# RPi_Zero_W_Breakout.net
KiCad netlist of a schematic drawn in EAGLE
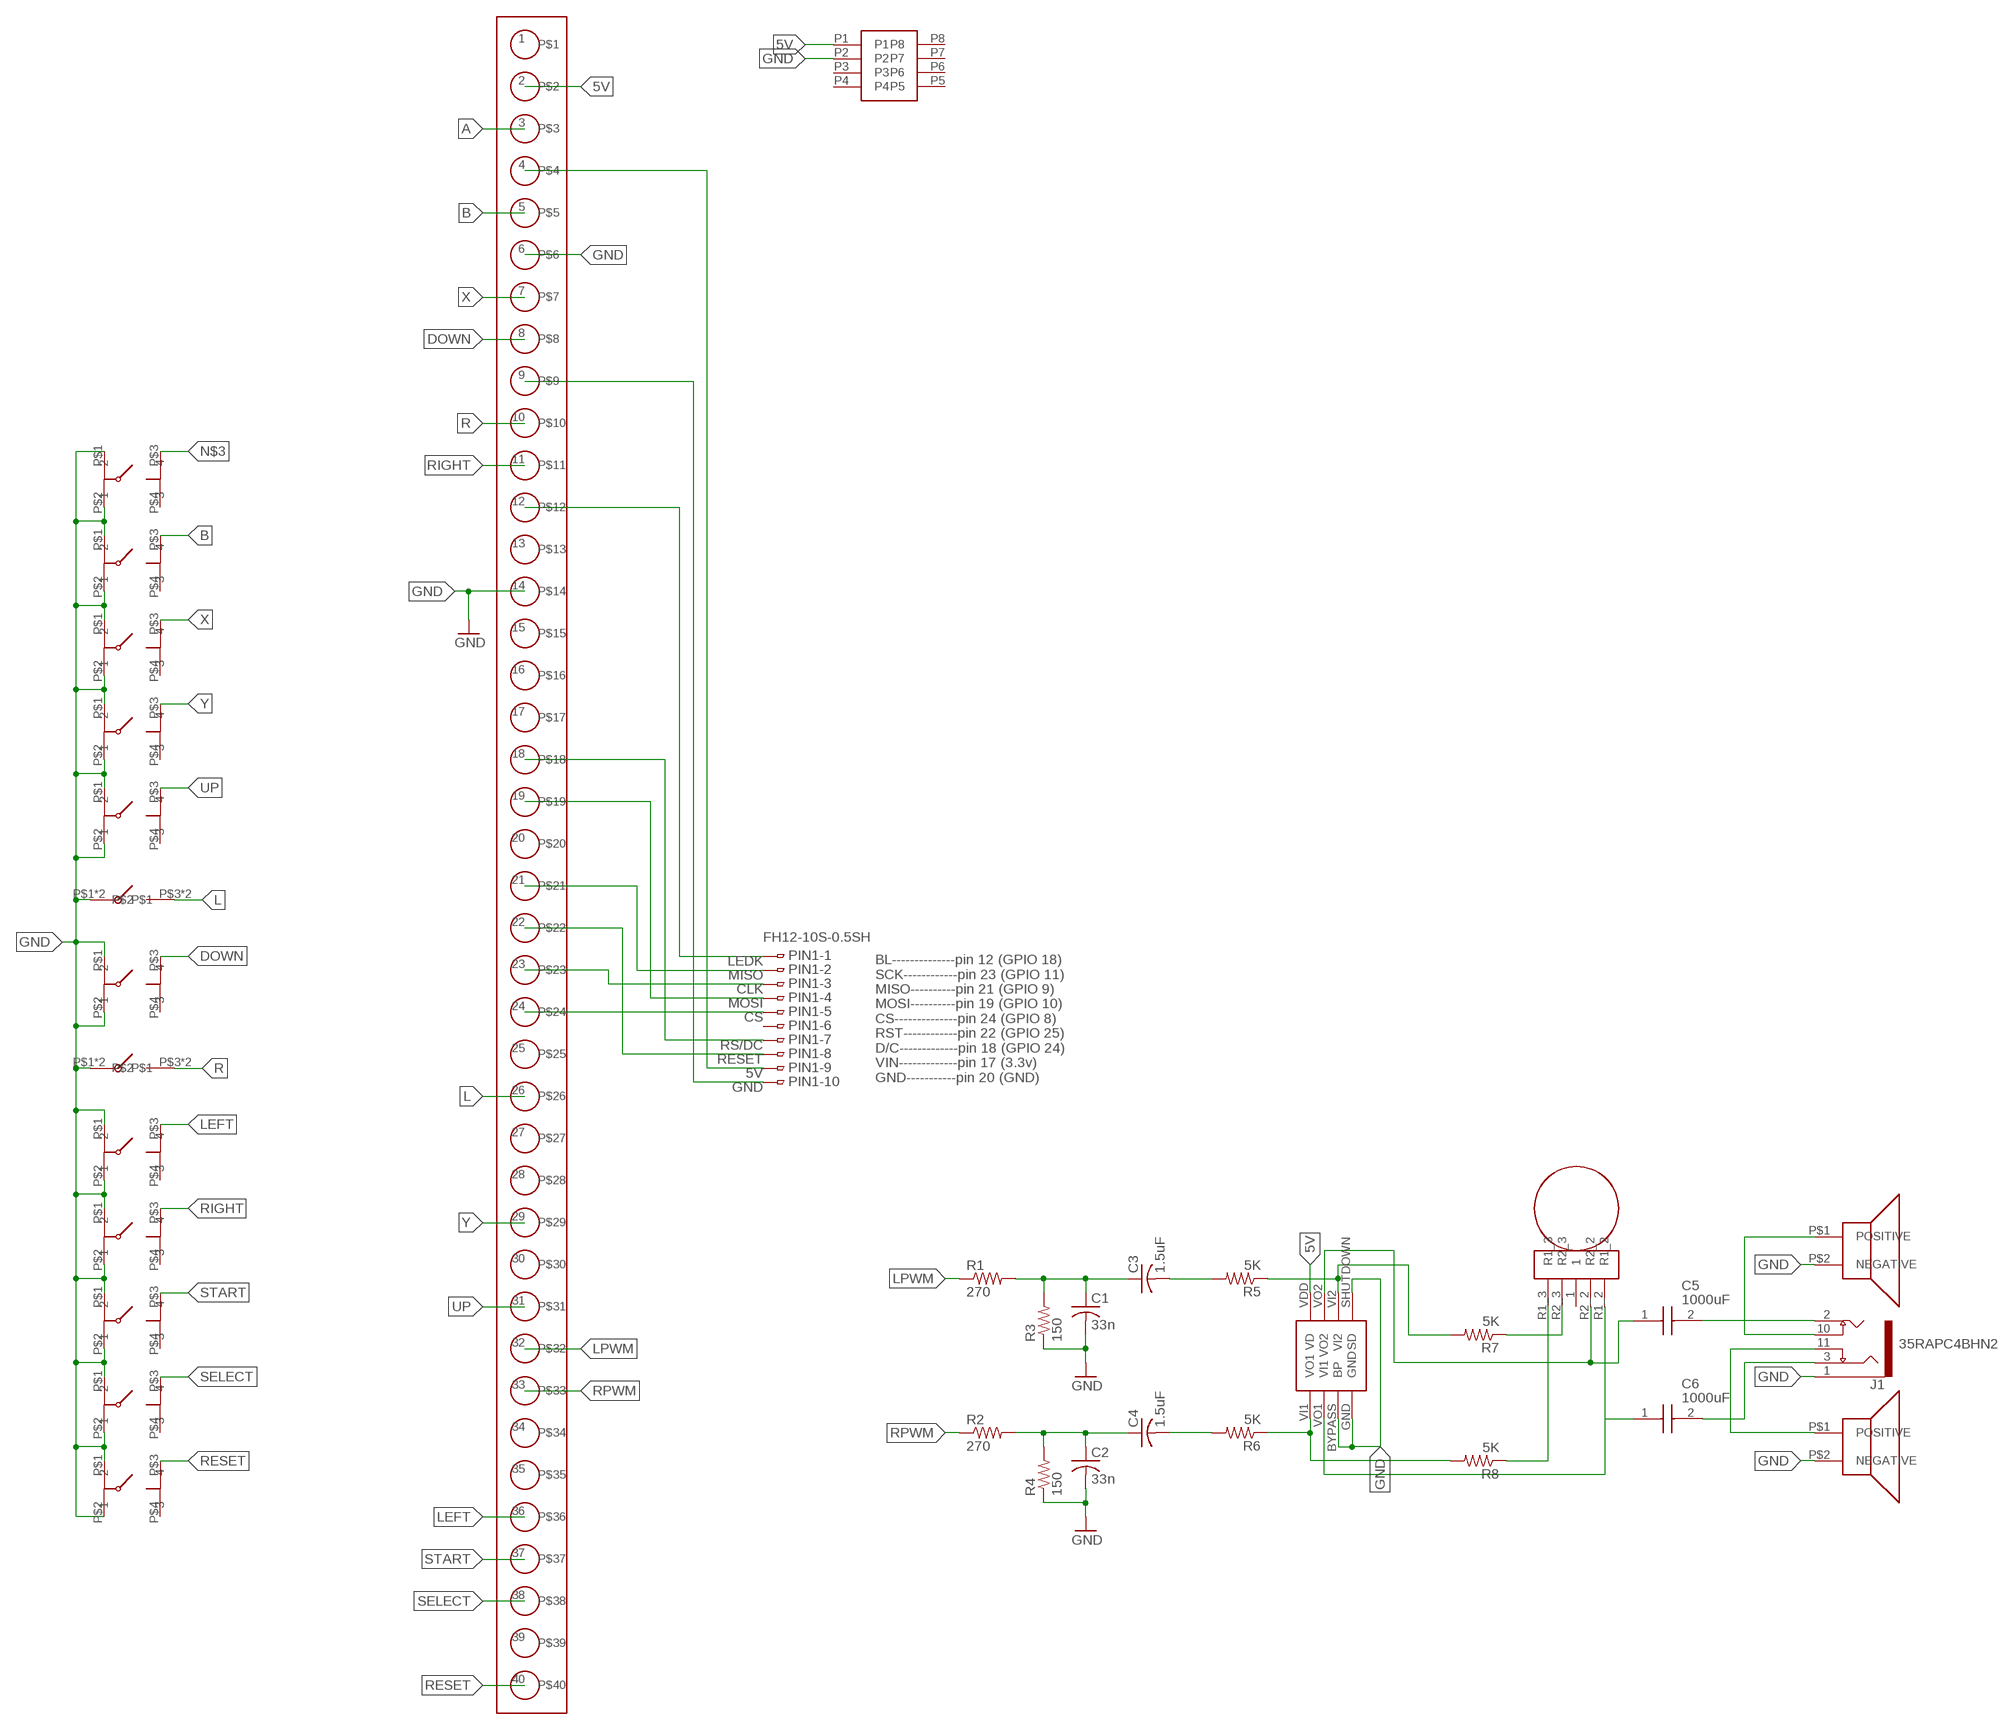
[diagram p0: schematic, sheet 1]

(export (version "E")
  (design (tool "Eeschema 10.0.6"))
  (components
    (comp (ref "A")
      (value "SWITCHTACTILESPST-NO0.05A24V")
      (footprint "eagle-import:1825910")
      (libsource (lib "eagle-import") (part "SWITCH TACTILE SPST-NO 0.05A 24V_SWITCHTACTILESPST-NO0.05A24V"))
    )
    (comp (ref "B")
      (value "SWITCHTACTILESPST-NO0.05A24V")
      (footprint "eagle-import:1825910")
      (libsource (lib "eagle-import") (part "SWITCH TACTILE SPST-NO 0.05A 24V_SWITCHTACTILESPST-NO0.05A24V"))
    )
    (comp (ref "C1")
      (value "33n")
      (footprint "eagle-import:C0805K")
      (libsource (lib "eagle-import") (part "C-USC0805K"))
    )
    (comp (ref "C2")
      (value "33n")
      (footprint "eagle-import:C0805K")
      (libsource (lib "eagle-import") (part "C-USC0805K"))
    )
    (comp (ref "C3")
      (value "1.5uF")
      (footprint "eagle-import:C0805K")
      (libsource (lib "eagle-import") (part "C-USC0805K"))
    )
    (comp (ref "C4")
      (value "1.5uF")
      (footprint "eagle-import:C0805K")
      (libsource (lib "eagle-import") (part "C-USC0805K"))
    )
    (comp (ref "C5")
      (value "1000uF")
      (footprint "eagle-import:UWT(8X10)")
      (fields
        (field (name "MANUFACTURER_PART_NUMBER") "UWT0J102MNL1GS")
        (field (name "MOUSER_PART_NUMBER") "647-UWT0J102MNL1S")
      )
      (libsource (lib "eagle-import") (part "UWT0J102MNL1GS"))
    )
    (comp (ref "C6")
      (value "1000uF")
      (footprint "eagle-import:UWT(8X10)")
      (fields
        (field (name "MANUFACTURER_PART_NUMBER") "UWT0J102MNL1GS")
        (field (name "MOUSER_PART_NUMBER") "647-UWT0J102MNL1S")
      )
      (libsource (lib "eagle-import") (part "UWT0J102MNL1GS"))
    )
    (comp (ref "DOWN")
      (value "SWITCHTACTILESPST-NO0.05A24V")
      (footprint "eagle-import:1825910")
      (libsource (lib "eagle-import") (part "SWITCH TACTILE SPST-NO 0.05A 24V_SWITCHTACTILESPST-NO0.05A24V"))
    )
    (comp (ref "J1")
      (value "35RAPC4BHN2")
      (footprint "eagle-import:SWITCHCRAFT_35RAPC4BHN2")
      (fields (field (name "DIGI-KEY_PART_NUMBER") "SC1459-ND") (field (name "MF") "Switchcraft"))
      (libsource (lib "eagle-import") (part "35RAPC4BHN2"))
    )
    (comp (ref "L")
      (value "SWITCHTACTILESPST-NO0.05A24V")
      (footprint "eagle-import:1825027-6")
      (libsource (lib "eagle-import") (part "SWITCHTACTILESPST-NO0.05A24V"))
    )
    (comp (ref "LEFT")
      (value "SWITCHTACTILESPST-NO0.05A24V")
      (footprint "eagle-import:1825910")
      (libsource (lib "eagle-import") (part "SWITCH TACTILE SPST-NO 0.05A 24V_SWITCHTACTILESPST-NO0.05A24V"))
    )
    (comp (ref "LSPK")
      (value "SP-1208")
      (footprint "eagle-import:SP-1208")
      (libsource (lib "eagle-import") (part "SP-1208"))
    )
    (comp (ref "PIN1")
      (value "FH12-10S-0.5SH")
      (footprint "eagle-import:FH12-10S-0.5SH")
      (fields (field (name "MPN") "FH12-10S-0.5SH(55)"))
      (libsource (lib "eagle-import") (part "FH12-10S-0.5SH"))
    )
    (comp (ref "R")
      (value "SWITCHTACTILESPST-NO0.05A24V")
      (footprint "eagle-import:1825027-6")
      (libsource (lib "eagle-import") (part "SWITCHTACTILESPST-NO0.05A24V"))
    )
    (comp (ref "R1")
      (value "270")
      (footprint "eagle-import:R0805")
      (libsource (lib "eagle-import") (part "R-US_R0805"))
    )
    (comp (ref "R2")
      (value "270")
      (footprint "eagle-import:R0805")
      (libsource (lib "eagle-import") (part "R-US_R0805"))
    )
    (comp (ref "R3")
      (value "150")
      (footprint "eagle-import:R0805")
      (libsource (lib "eagle-import") (part "R-US_R0805"))
    )
    (comp (ref "R4")
      (value "150")
      (footprint "eagle-import:R0805")
      (libsource (lib "eagle-import") (part "R-US_R0805"))
    )
    (comp (ref "R5")
      (value "5K")
      (footprint "eagle-import:R0805")
      (libsource (lib "eagle-import") (part "R-US_R0805"))
    )
    (comp (ref "R6")
      (value "5K")
      (footprint "eagle-import:R0805")
      (libsource (lib "eagle-import") (part "R-US_R0805"))
    )
    (comp (ref "R7")
      (value "5K")
      (footprint "eagle-import:R0805")
      (libsource (lib "eagle-import") (part "R-US_R0805"))
    )
    (comp (ref "R8")
      (value "5K")
      (footprint "eagle-import:R0805")
      (libsource (lib "eagle-import") (part "R-US_R0805"))
    )
    (comp (ref "RESET")
      (value "SWITCHTACTILESPST-NO0.05A24V")
      (footprint "eagle-import:1825910")
      (libsource (lib "eagle-import") (part "SWITCH TACTILE SPST-NO 0.05A 24V_SWITCHTACTILESPST-NO0.05A24V"))
    )
    (comp (ref "RIGHT")
      (value "SWITCHTACTILESPST-NO0.05A24V")
      (footprint "eagle-import:1825910")
      (libsource (lib "eagle-import") (part "SWITCH TACTILE SPST-NO 0.05A 24V_SWITCHTACTILESPST-NO0.05A24V"))
    )
    (comp (ref "RSPK")
      (value "SP-1208")
      (footprint "eagle-import:SP-1208")
      (libsource (lib "eagle-import") (part "SP-1208"))
    )
    (comp (ref "SELECT")
      (value "SWITCHTACTILESPST-NO0.05A24V")
      (footprint "eagle-import:1825910")
      (libsource (lib "eagle-import") (part "SWITCH TACTILE SPST-NO 0.05A 24V_SWITCHTACTILESPST-NO0.05A24V"))
    )
    (comp (ref "START")
      (value "SWITCHTACTILESPST-NO0.05A24V")
      (footprint "eagle-import:1825910")
      (libsource (lib "eagle-import") (part "SWITCH TACTILE SPST-NO 0.05A 24V_SWITCHTACTILESPST-NO0.05A24V"))
    )
    (comp (ref "U$1")
      (value "20X20.1HEADERS")
      (footprint "eagle-import:20X20.1_MALEHEADERS")
      (libsource (lib "eagle-import") (part "20X20.1HEADERS"))
    )
    (comp (ref "U$2")
      (value "LM4810MM/NOPBCT-ND")
      (footprint "eagle-import:NOPBCT-ND")
      (libsource (lib "eagle-import") (part "LM4810MM/NOPBCT-ND"))
    )
    (comp (ref "U$3")
      (value "M22-6340442")
      (footprint "eagle-import:M22-6340442")
      (libsource (lib "eagle-import") (part "M22-6340442"))
    )
    (comp (ref "U$4")
      (value "RK14J12A0A0K")
      (footprint "eagle-import:RK14J12A0A0K")
      (libsource (lib "eagle-import") (part "RK14J12A0A0K"))
    )
    (comp (ref "UP")
      (value "SWITCHTACTILESPST-NO0.05A24V")
      (footprint "eagle-import:1825910")
      (libsource (lib "eagle-import") (part "SWITCH TACTILE SPST-NO 0.05A 24V_SWITCHTACTILESPST-NO0.05A24V"))
    )
    (comp (ref "X")
      (value "SWITCHTACTILESPST-NO0.05A24V")
      (footprint "eagle-import:1825910")
      (libsource (lib "eagle-import") (part "SWITCH TACTILE SPST-NO 0.05A 24V_SWITCHTACTILESPST-NO0.05A24V"))
    )
    (comp (ref "Y")
      (value "SWITCHTACTILESPST-NO0.05A24V")
      (footprint "eagle-import:1825910")
      (libsource (lib "eagle-import") (part "SWITCH TACTILE SPST-NO 0.05A 24V_SWITCHTACTILESPST-NO0.05A24V"))
    )
  )
  (nets
    (net (code "1") (name "/CLK") (class "Default")
      (node (ref "PIN1") (pin "3") (pinfunction "1_3") (pintype "passive"))
      (node (ref "U$1") (pin "23") (pinfunction "P$23_23") (pintype "bidirectional"))
    )
    (net (code "2") (name "/CS") (class "Default")
      (node (ref "PIN1") (pin "5") (pinfunction "1_5") (pintype "passive"))
      (node (ref "U$1") (pin "24") (pinfunction "P$24_24") (pintype "bidirectional"))
    )
    (net (code "3") (name "/LEDK") (class "Default")
      (node (ref "PIN1") (pin "1") (pinfunction "1_1") (pintype "passive"))
      (node (ref "U$1") (pin "12") (pinfunction "P$12_12") (pintype "bidirectional"))
    )
    (net (code "4") (name "/MISO") (class "Default")
      (node (ref "PIN1") (pin "2") (pinfunction "1_2") (pintype "passive"))
      (node (ref "U$1") (pin "21") (pinfunction "P$21_21") (pintype "bidirectional"))
    )
    (net (code "5") (name "/MOSI") (class "Default")
      (node (ref "PIN1") (pin "4") (pinfunction "1_4") (pintype "passive"))
      (node (ref "U$1") (pin "19") (pinfunction "P$19_19") (pintype "bidirectional"))
    )
    (net (code "6") (name "/RS{slash}DC") (class "Default")
      (node (ref "PIN1") (pin "7") (pinfunction "1_7") (pintype "passive"))
      (node (ref "U$1") (pin "18") (pinfunction "P$18_18") (pintype "bidirectional"))
    )
    (net (code "7") (name "5V") (class "Default")
      (node (ref "PIN1") (pin "9") (pinfunction "1_9") (pintype "passive"))
      (node (ref "U$1") (pin "2") (pinfunction "P$2_2") (pintype "bidirectional"))
      (node (ref "U$1") (pin "4") (pinfunction "P$4_4") (pintype "bidirectional"))
      (node (ref "U$2") (pin "VDD") (pinfunction "VD_VDD") (pintype "bidirectional"))
      (node (ref "U$3") (pin "P1") (pinfunction "P1_P1") (pintype "bidirectional"))
    )
    (net (code "8") (name "A") (class "Default")
      (node (ref "U$1") (pin "3") (pinfunction "P$3_3") (pintype "bidirectional"))
    )
    (net (code "9") (name "B") (class "Default")
      (node (ref "B") (pin "P$3") (pinfunction "3_P$3") (pintype "bidirectional"))
      (node (ref "U$1") (pin "5") (pinfunction "P$5_5") (pintype "bidirectional"))
    )
    (net (code "10") (name "DOWN") (class "Default")
      (node (ref "DOWN") (pin "P$3") (pinfunction "3_P$3") (pintype "bidirectional"))
      (node (ref "U$1") (pin "8") (pinfunction "P$8_8") (pintype "bidirectional"))
    )
    (net (code "11") (name "GND") (class "Default")
      (node (ref "A") (pin "P$1") (pinfunction "1_P$1") (pintype "bidirectional"))
      (node (ref "A") (pin "P$2") (pinfunction "2_P$2") (pintype "bidirectional"))
      (node (ref "B") (pin "P$1") (pinfunction "1_P$1") (pintype "bidirectional"))
      (node (ref "B") (pin "P$2") (pinfunction "2_P$2") (pintype "bidirectional"))
      (node (ref "C1") (pin "2") (pinfunction "2_2") (pintype "passive"))
      (node (ref "C2") (pin "2") (pinfunction "2_2") (pintype "passive"))
      (node (ref "DOWN") (pin "P$1") (pinfunction "1_P$1") (pintype "bidirectional"))
      (node (ref "DOWN") (pin "P$2") (pinfunction "2_P$2") (pintype "bidirectional"))
      (node (ref "J1") (pin "1") (pinfunction "1_1") (pintype "passive"))
      (node (ref "L") (pin "P$1") (pinfunction "P$1_P$1") (pintype "bidirectional"))
      (node (ref "L") (pin "P$2") (pinfunction "P$1_P$2") (pintype "bidirectional"))
      (node (ref "LEFT") (pin "P$1") (pinfunction "1_P$1") (pintype "bidirectional"))
      (node (ref "LEFT") (pin "P$2") (pinfunction "2_P$2") (pintype "bidirectional"))
      (node (ref "LSPK") (pin "P$2") (pinfunction "NEGATIVE_P$2") (pintype "bidirectional"))
      (node (ref "PIN1") (pin "10") (pinfunction "1_10") (pintype "passive"))
      (node (ref "R") (pin "P$1") (pinfunction "P$1_P$1") (pintype "bidirectional"))
      (node (ref "R") (pin "P$2") (pinfunction "P$1_P$2") (pintype "bidirectional"))
      (node (ref "R3") (pin "1") (pinfunction "1_1") (pintype "passive"))
      (node (ref "R4") (pin "1") (pinfunction "1_1") (pintype "passive"))
      (node (ref "RESET") (pin "P$1") (pinfunction "1_P$1") (pintype "bidirectional"))
      (node (ref "RESET") (pin "P$2") (pinfunction "2_P$2") (pintype "bidirectional"))
      (node (ref "RIGHT") (pin "P$1") (pinfunction "1_P$1") (pintype "bidirectional"))
      (node (ref "RIGHT") (pin "P$2") (pinfunction "2_P$2") (pintype "bidirectional"))
      (node (ref "RSPK") (pin "P$2") (pinfunction "NEGATIVE_P$2") (pintype "bidirectional"))
      (node (ref "SELECT") (pin "P$1") (pinfunction "1_P$1") (pintype "bidirectional"))
      (node (ref "SELECT") (pin "P$2") (pinfunction "2_P$2") (pintype "bidirectional"))
      (node (ref "START") (pin "P$1") (pinfunction "1_P$1") (pintype "bidirectional"))
      (node (ref "START") (pin "P$2") (pinfunction "2_P$2") (pintype "bidirectional"))
      (node (ref "U$1") (pin "14") (pinfunction "P$14_14") (pintype "bidirectional"))
      (node (ref "U$1") (pin "6") (pinfunction "P$6_6") (pintype "bidirectional"))
      (node (ref "U$1") (pin "9") (pinfunction "P$9_9") (pintype "bidirectional"))
      (node (ref "U$2") (pin "BYPASS") (pinfunction "BP_BYPASS") (pintype "bidirectional"))
      (node (ref "U$2") (pin "GND") (pinfunction "GND_GND") (pintype "bidirectional"))
      (node (ref "U$2") (pin "SHUTDOWN") (pinfunction "SD_SHUTDOWN") (pintype "bidirectional"))
      (node (ref "U$3") (pin "P2") (pinfunction "P2_P2") (pintype "bidirectional"))
      (node (ref "UP") (pin "P$1") (pinfunction "1_P$1") (pintype "bidirectional"))
      (node (ref "UP") (pin "P$2") (pinfunction "2_P$2") (pintype "bidirectional"))
      (node (ref "X") (pin "P$1") (pinfunction "1_P$1") (pintype "bidirectional"))
      (node (ref "X") (pin "P$2") (pinfunction "2_P$2") (pintype "bidirectional"))
      (node (ref "Y") (pin "P$1") (pinfunction "1_P$1") (pintype "bidirectional"))
      (node (ref "Y") (pin "P$2") (pinfunction "2_P$2") (pintype "bidirectional"))
    )
    (net (code "12") (name "L") (class "Default")
      (node (ref "L") (pin "P$3") (pinfunction "P$2_P$3") (pintype "bidirectional"))
      (node (ref "L") (pin "P$4") (pinfunction "P$2_P$4") (pintype "bidirectional"))
      (node (ref "U$1") (pin "26") (pinfunction "P$26_26") (pintype "bidirectional"))
    )
    (net (code "13") (name "LEFT") (class "Default")
      (node (ref "LEFT") (pin "P$3") (pinfunction "3_P$3") (pintype "bidirectional"))
      (node (ref "U$1") (pin "36") (pinfunction "P$36_36") (pintype "bidirectional"))
    )
    (net (code "14") (name "LPWM") (class "Default")
      (node (ref "R1") (pin "1") (pinfunction "1_1") (pintype "passive"))
      (node (ref "U$1") (pin "32") (pinfunction "P$32_32") (pintype "bidirectional"))
    )
    (net (code "15") (name "N$3") (class "Default")
      (node (ref "A") (pin "P$3") (pinfunction "3_P$3") (pintype "bidirectional"))
    )
    (net (code "16") (name "Net-(C1-Pad1)") (class "Default")
      (node (ref "C1") (pin "1") (pinfunction "1_1") (pintype "passive"))
      (node (ref "C3") (pin "1") (pinfunction "1_1") (pintype "passive"))
      (node (ref "R1") (pin "2") (pinfunction "2_2") (pintype "passive"))
      (node (ref "R3") (pin "2") (pinfunction "2_2") (pintype "passive"))
    )
    (net (code "17") (name "Net-(C2-Pad1)") (class "Default")
      (node (ref "C2") (pin "1") (pinfunction "1_1") (pintype "passive"))
      (node (ref "C4") (pin "1") (pinfunction "1_1") (pintype "passive"))
      (node (ref "R2") (pin "2") (pinfunction "2_2") (pintype "passive"))
      (node (ref "R4") (pin "2") (pinfunction "2_2") (pintype "passive"))
    )
    (net (code "18") (name "Net-(C3-Pad2)") (class "Default")
      (node (ref "C3") (pin "2") (pinfunction "2_2") (pintype "passive"))
      (node (ref "R5") (pin "2") (pinfunction "2_2") (pintype "passive"))
    )
    (net (code "19") (name "Net-(C4-Pad2)") (class "Default")
      (node (ref "C4") (pin "2") (pinfunction "2_2") (pintype "passive"))
      (node (ref "R6") (pin "2") (pinfunction "2_2") (pintype "passive"))
    )
    (net (code "20") (name "Net-(C5-+)") (class "Default")
      (node (ref "C5") (pin "1") (pinfunction "+_1") (pintype "bidirectional"))
      (node (ref "U$2") (pin "VO2") (pinfunction "VO2_VO2") (pintype "bidirectional"))
      (node (ref "U$4") (pin "R2_2") (pinfunction "R2_2_R2_2") (pintype "bidirectional"))
    )
    (net (code "21") (name "Net-(C5--)") (class "Default")
      (node (ref "C5") (pin "2") (pinfunction "-_2") (pintype "bidirectional"))
      (node (ref "J1") (pin "2") (pinfunction "2_2") (pintype "passive"))
    )
    (net (code "22") (name "Net-(C6-+)") (class "Default")
      (node (ref "C6") (pin "1") (pinfunction "+_1") (pintype "bidirectional"))
      (node (ref "U$2") (pin "VO1") (pinfunction "VI1_VO1") (pintype "bidirectional"))
      (node (ref "U$4") (pin "R1_2") (pinfunction "R1_2_R1_2") (pintype "bidirectional"))
    )
    (net (code "23") (name "Net-(C6--)") (class "Default")
      (node (ref "C6") (pin "2") (pinfunction "-_2") (pintype "bidirectional"))
      (node (ref "J1") (pin "3") (pinfunction "3_3") (pintype "passive"))
    )
    (net (code "24") (name "Net-(LSPK-POSITIVE)") (class "Default")
      (node (ref "J1") (pin "11") (pinfunction "11_11") (pintype "passive"))
      (node (ref "LSPK") (pin "P$1") (pinfunction "POSITIVE_P$1") (pintype "bidirectional"))
    )
    (net (code "25") (name "Net-(R5-Pad1)") (class "Default")
      (node (ref "R5") (pin "1") (pinfunction "1_1") (pintype "passive"))
      (node (ref "R7") (pin "2") (pinfunction "2_2") (pintype "passive"))
      (node (ref "U$2") (pin "VI2") (pinfunction "VI2_VI2") (pintype "bidirectional"))
    )
    (net (code "26") (name "Net-(R7-Pad1)") (class "Default")
      (node (ref "R7") (pin "1") (pinfunction "1_1") (pintype "passive"))
      (node (ref "U$4") (pin "R2_3") (pinfunction "R2_3_R2_3") (pintype "bidirectional"))
    )
    (net (code "27") (name "Net-(R8-Pad1)") (class "Default")
      (node (ref "R8") (pin "1") (pinfunction "1_1") (pintype "passive"))
      (node (ref "U$4") (pin "R1_3") (pinfunction "R1_3_R1_3") (pintype "bidirectional"))
    )
    (net (code "28") (name "Net-(RSPK-POSITIVE)") (class "Default")
      (node (ref "J1") (pin "10") (pinfunction "10_10") (pintype "passive"))
      (node (ref "RSPK") (pin "P$1") (pinfunction "POSITIVE_P$1") (pintype "bidirectional"))
    )
    (net (code "29") (name "Net-(U$2-VO1)") (class "Default")
      (node (ref "R6") (pin "1") (pinfunction "1_1") (pintype "passive"))
      (node (ref "R8") (pin "2") (pinfunction "2_2") (pintype "passive"))
      (node (ref "U$2") (pin "VI1") (pinfunction "VO1_VI1") (pintype "bidirectional"))
    )
    (net (code "30") (name "R") (class "Default")
      (node (ref "R") (pin "P$3") (pinfunction "P$2_P$3") (pintype "bidirectional"))
      (node (ref "R") (pin "P$4") (pinfunction "P$2_P$4") (pintype "bidirectional"))
      (node (ref "U$1") (pin "10") (pinfunction "P$10_10") (pintype "bidirectional"))
    )
    (net (code "31") (name "RESET") (class "Default")
      (node (ref "PIN1") (pin "8") (pinfunction "1_8") (pintype "passive"))
      (node (ref "RESET") (pin "P$3") (pinfunction "3_P$3") (pintype "bidirectional"))
      (node (ref "U$1") (pin "22") (pinfunction "P$22_22") (pintype "bidirectional"))
      (node (ref "U$1") (pin "40") (pinfunction "P$40_40") (pintype "bidirectional"))
    )
    (net (code "32") (name "RIGHT") (class "Default")
      (node (ref "RIGHT") (pin "P$3") (pinfunction "3_P$3") (pintype "bidirectional"))
      (node (ref "U$1") (pin "11") (pinfunction "P$11_11") (pintype "bidirectional"))
    )
    (net (code "33") (name "RPWM") (class "Default")
      (node (ref "R2") (pin "1") (pinfunction "1_1") (pintype "passive"))
      (node (ref "U$1") (pin "33") (pinfunction "P$33_33") (pintype "bidirectional"))
    )
    (net (code "34") (name "SELECT") (class "Default")
      (node (ref "SELECT") (pin "P$3") (pinfunction "3_P$3") (pintype "bidirectional"))
      (node (ref "U$1") (pin "38") (pinfunction "P$38_38") (pintype "bidirectional"))
    )
    (net (code "35") (name "START") (class "Default")
      (node (ref "START") (pin "P$3") (pinfunction "3_P$3") (pintype "bidirectional"))
      (node (ref "U$1") (pin "37") (pinfunction "P$37_37") (pintype "bidirectional"))
    )
    (net (code "36") (name "UP") (class "Default")
      (node (ref "U$1") (pin "31") (pinfunction "P$31_31") (pintype "bidirectional"))
      (node (ref "UP") (pin "P$3") (pinfunction "3_P$3") (pintype "bidirectional"))
    )
    (net (code "37") (name "X") (class "Default")
      (node (ref "U$1") (pin "7") (pinfunction "P$7_7") (pintype "bidirectional"))
      (node (ref "X") (pin "P$3") (pinfunction "3_P$3") (pintype "bidirectional"))
    )
    (net (code "38") (name "Y") (class "Default")
      (node (ref "U$1") (pin "29") (pinfunction "P$29_29") (pintype "bidirectional"))
      (node (ref "Y") (pin "P$3") (pinfunction "3_P$3") (pintype "bidirectional"))
    )
    (net (code "39") (name "unconnected-(A-4-PadP$4)") (class "Default")
      (node (ref "A") (pin "P$4") (pinfunction "4_P$4") (pintype "bidirectional"))
    )
    (net (code "40") (name "unconnected-(B-4-PadP$4)") (class "Default")
      (node (ref "B") (pin "P$4") (pinfunction "4_P$4") (pintype "bidirectional"))
    )
    (net (code "41") (name "unconnected-(DOWN-4-PadP$4)") (class "Default")
      (node (ref "DOWN") (pin "P$4") (pinfunction "4_P$4") (pintype "bidirectional"))
    )
    (net (code "42") (name "unconnected-(LEFT-4-PadP$4)") (class "Default")
      (node (ref "LEFT") (pin "P$4") (pinfunction "4_P$4") (pintype "bidirectional"))
    )
    (net (code "43") (name "unconnected-(PIN1G-1-Pad6)") (class "Default")
      (node (ref "PIN1") (pin "6") (pinfunction "1_6") (pintype "passive"))
    )
    (net (code "44") (name "unconnected-(RESET-4-PadP$4)") (class "Default")
      (node (ref "RESET") (pin "P$4") (pinfunction "4_P$4") (pintype "bidirectional"))
    )
    (net (code "45") (name "unconnected-(RIGHT-4-PadP$4)") (class "Default")
      (node (ref "RIGHT") (pin "P$4") (pinfunction "4_P$4") (pintype "bidirectional"))
    )
    (net (code "46") (name "unconnected-(SELECT-4-PadP$4)") (class "Default")
      (node (ref "SELECT") (pin "P$4") (pinfunction "4_P$4") (pintype "bidirectional"))
    )
    (net (code "47") (name "unconnected-(START-4-PadP$4)") (class "Default")
      (node (ref "START") (pin "P$4") (pinfunction "4_P$4") (pintype "bidirectional"))
    )
    (net (code "48") (name "unconnected-(U$1-P$1-Pad1)") (class "Default")
      (node (ref "U$1") (pin "1") (pinfunction "P$1_1") (pintype "bidirectional"))
    )
    (net (code "49") (name "unconnected-(U$1-P$13-Pad13)") (class "Default")
      (node (ref "U$1") (pin "13") (pinfunction "P$13_13") (pintype "bidirectional"))
    )
    (net (code "50") (name "unconnected-(U$1-P$15-Pad15)") (class "Default")
      (node (ref "U$1") (pin "15") (pinfunction "P$15_15") (pintype "bidirectional"))
    )
    (net (code "51") (name "unconnected-(U$1-P$16-Pad16)") (class "Default")
      (node (ref "U$1") (pin "16") (pinfunction "P$16_16") (pintype "bidirectional"))
    )
    (net (code "52") (name "unconnected-(U$1-P$17-Pad17)") (class "Default")
      (node (ref "U$1") (pin "17") (pinfunction "P$17_17") (pintype "bidirectional"))
    )
    (net (code "53") (name "unconnected-(U$1-P$20-Pad20)") (class "Default")
      (node (ref "U$1") (pin "20") (pinfunction "P$20_20") (pintype "bidirectional"))
    )
    (net (code "54") (name "unconnected-(U$1-P$25-Pad25)") (class "Default")
      (node (ref "U$1") (pin "25") (pinfunction "P$25_25") (pintype "bidirectional"))
    )
    (net (code "55") (name "unconnected-(U$1-P$27-Pad27)") (class "Default")
      (node (ref "U$1") (pin "27") (pinfunction "P$27_27") (pintype "bidirectional"))
    )
    (net (code "56") (name "unconnected-(U$1-P$28-Pad28)") (class "Default")
      (node (ref "U$1") (pin "28") (pinfunction "P$28_28") (pintype "bidirectional"))
    )
    (net (code "57") (name "unconnected-(U$1-P$30-Pad30)") (class "Default")
      (node (ref "U$1") (pin "30") (pinfunction "P$30_30") (pintype "bidirectional"))
    )
    (net (code "58") (name "unconnected-(U$1-P$34-Pad34)") (class "Default")
      (node (ref "U$1") (pin "34") (pinfunction "P$34_34") (pintype "bidirectional"))
    )
    (net (code "59") (name "unconnected-(U$1-P$35-Pad35)") (class "Default")
      (node (ref "U$1") (pin "35") (pinfunction "P$35_35") (pintype "bidirectional"))
    )
    (net (code "60") (name "unconnected-(U$1-P$39-Pad39)") (class "Default")
      (node (ref "U$1") (pin "39") (pinfunction "P$39_39") (pintype "bidirectional"))
    )
    (net (code "61") (name "unconnected-(U$3-PadP3)") (class "Default")
      (node (ref "U$3") (pin "P3") (pinfunction "P3_P3") (pintype "bidirectional"))
    )
    (net (code "62") (name "unconnected-(U$3-PadP4)") (class "Default")
      (node (ref "U$3") (pin "P4") (pinfunction "P4_P4") (pintype "bidirectional"))
    )
    (net (code "63") (name "unconnected-(U$3-PadP5)") (class "Default")
      (node (ref "U$3") (pin "P5") (pinfunction "P5_P5") (pintype "bidirectional"))
    )
    (net (code "64") (name "unconnected-(U$3-PadP6)") (class "Default")
      (node (ref "U$3") (pin "P6") (pinfunction "P6_P6") (pintype "bidirectional"))
    )
    (net (code "65") (name "unconnected-(U$3-PadP7)") (class "Default")
      (node (ref "U$3") (pin "P7") (pinfunction "P7_P7") (pintype "bidirectional"))
    )
    (net (code "66") (name "unconnected-(U$3-PadP8)") (class "Default")
      (node (ref "U$3") (pin "P8") (pinfunction "P8_P8") (pintype "bidirectional"))
    )
    (net (code "67") (name "unconnected-(U$4-Pad1)") (class "Default")
      (node (ref "U$4") (pin "1") (pinfunction "1_1") (pintype "bidirectional"))
    )
    (net (code "68") (name "unconnected-(UP-4-PadP$4)") (class "Default")
      (node (ref "UP") (pin "P$4") (pinfunction "4_P$4") (pintype "bidirectional"))
    )
    (net (code "69") (name "unconnected-(X-4-PadP$4)") (class "Default")
      (node (ref "X") (pin "P$4") (pinfunction "4_P$4") (pintype "bidirectional"))
    )
    (net (code "70") (name "unconnected-(Y-4-PadP$4)") (class "Default")
      (node (ref "Y") (pin "P$4") (pinfunction "4_P$4") (pintype "bidirectional"))
    )
  )
)
